# connect.net
KiCad netlist of a schematic drawn in Altium Designer
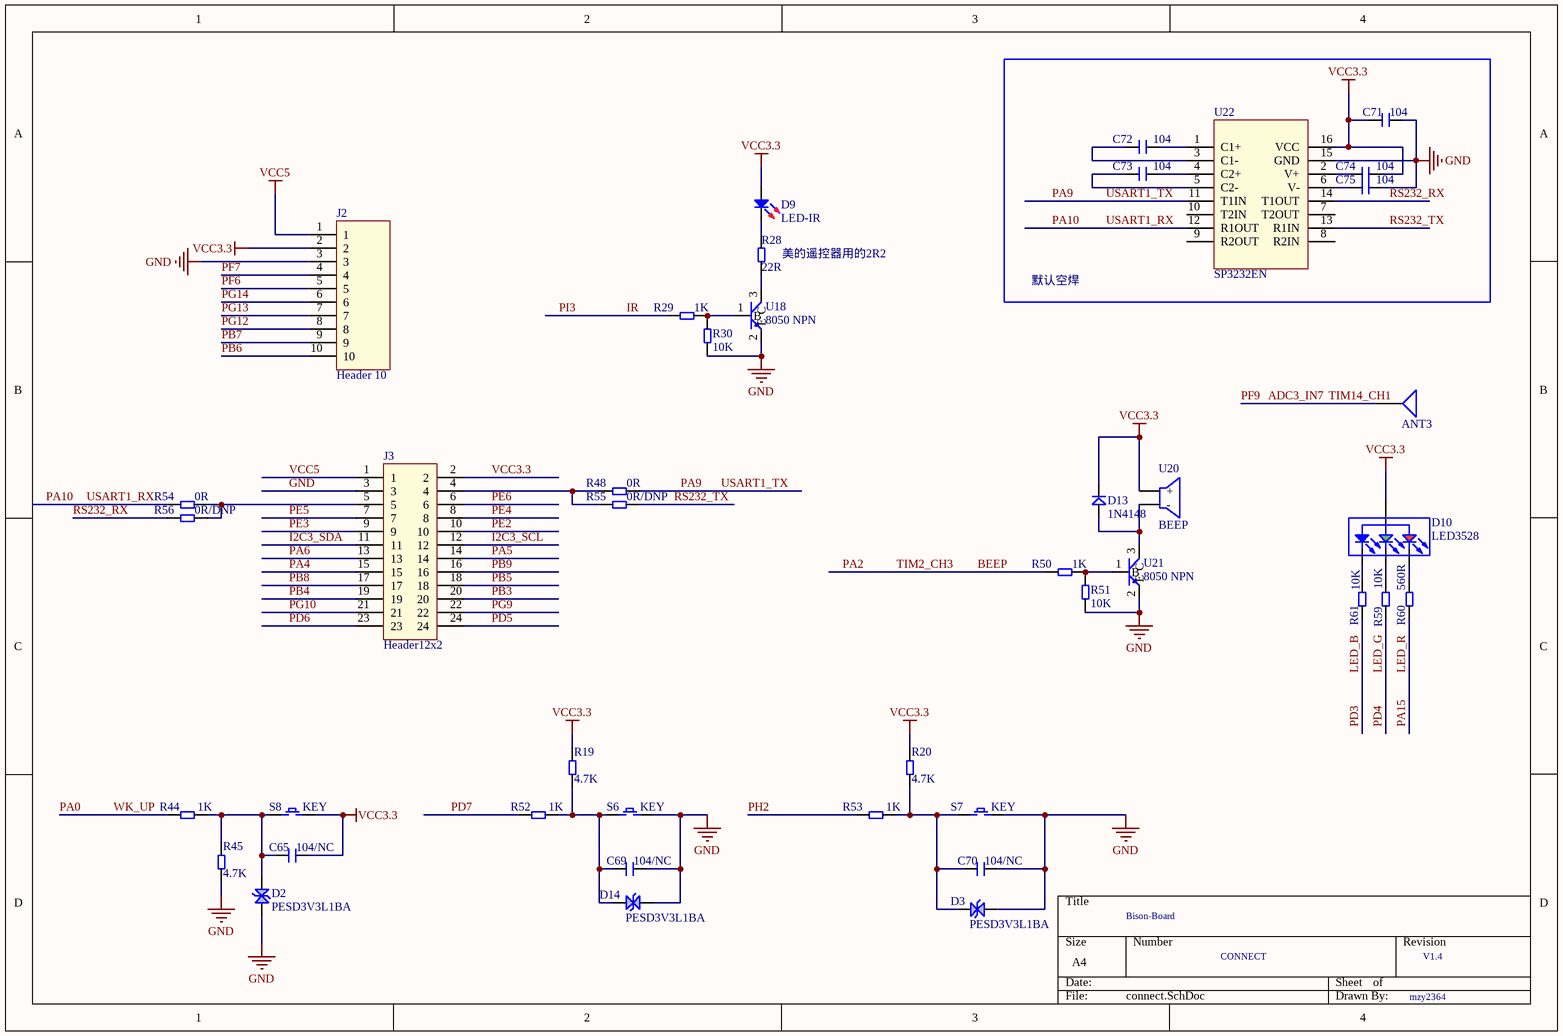
[diagram p0: connect.SchDoc]

(export (version "E")
  (design (tool "Eeschema 10.0.6"))
  (components
    (comp (ref "ANT3") (value "ANT") (footprint "ANT IPEX") (libsource (lib "squ-guiboard") (part "ANT")))
    (comp (ref "C65") (value "104/NC") (footprint "C 0603") (libsource (lib "squ-guiboard") (part "CAP")))
    (comp (ref "C69") (value "104/NC") (footprint "C 0603") (libsource (lib "squ-guiboard") (part "CAP")))
    (comp (ref "C70") (value "104/NC") (footprint "C 0603") (libsource (lib "squ-guiboard") (part "CAP")))
    (comp (ref "C71") (value "104") (footprint "C 0603") (libsource (lib "squ-guiboard") (part "CAP")))
    (comp (ref "C72") (value "104") (footprint "C 0603") (libsource (lib "squ-guiboard") (part "CAP")))
    (comp (ref "C73") (value "104") (footprint "C 0603") (libsource (lib "squ-guiboard") (part "CAP")))
    (comp (ref "C74") (value "104") (footprint "C 0603") (libsource (lib "squ-guiboard") (part "CAP")))
    (comp (ref "C75") (value "104") (footprint "C 0603") (libsource (lib "squ-guiboard") (part "CAP")))
    (comp (ref "D2")
      (value "PESD3V3L1BA")
      (footprint "SOD323")
      (description "双向TVS")
      (libsource (lib "Bison-Board") (part "D Schottky1"))
    )
    (comp (ref "D3")
      (value "PESD3V3L1BA")
      (footprint "SOD323")
      (description "双向TVS")
      (libsource (lib "Bison-Board") (part "D Schottky1"))
    )
    (comp (ref "D9") (value "LED-IR") (footprint "IR12-21C") (libsource (lib "squ-guiboard") (part "LED-IR")))
    (comp (ref "D10")
      (value "LED3528")
      (footprint "LED3528-4PIN")
      (libsource (lib "squ-guiboard") (part "LED3528"))
    )
    (comp (ref "D13") (value "1N4148") (footprint "SOD123") (libsource (lib "squ-guiboard") (part "Diode")))
    (comp (ref "D14")
      (value "PESD3V3L1BA")
      (footprint "SOD323")
      (description "双向TVS")
      (libsource (lib "Bison-Board") (part "D Schottky1"))
    )
    (comp (ref "J2")
      (value "Header 10")
      (footprint "HEADER 10")
      (libsource (lib "Bison-Board") (part "Header 10"))
    )
    (comp (ref "J3")
      (value "Header12x2")
      (footprint "HDR2.54-M-LS-2x12P")
      (libsource (lib "squ-guiboard") (part "Header12x2"))
    )
    (comp (ref "R19") (value "4.7K") (footprint "R 0603") (libsource (lib "squ-guiboard") (part "RES")))
    (comp (ref "R20") (value "4.7K") (footprint "R 0603") (libsource (lib "squ-guiboard") (part "RES")))
    (comp (ref "R28") (value "22R") (footprint "R 0603") (libsource (lib "Bison-Board") (part "RES")))
    (comp (ref "R29") (value "1K") (footprint "R 0603") (libsource (lib "Bison-Board") (part "RES")))
    (comp (ref "R30") (value "10K") (footprint "R 0603") (libsource (lib "Bison-Board") (part "RES")))
    (comp (ref "R44") (value "1K") (footprint "R 0603") (libsource (lib "squ-guiboard") (part "RES")))
    (comp (ref "R45") (value "4.7K") (footprint "R 0603") (libsource (lib "squ-guiboard") (part "RES")))
    (comp (ref "R48") (value "0R") (footprint "R 0603") (libsource (lib "Bison-Board") (part "RES")))
    (comp (ref "R50") (value "1K") (footprint "R 0603") (libsource (lib "Bison-Board") (part "RES")))
    (comp (ref "R51") (value "10K") (footprint "R 0603") (libsource (lib "Bison-Board") (part "RES")))
    (comp (ref "R52") (value "1K") (footprint "R 0603") (libsource (lib "squ-guiboard") (part "RES")))
    (comp (ref "R53") (value "1K") (footprint "R 0603") (libsource (lib "squ-guiboard") (part "RES")))
    (comp (ref "R54") (value "0R") (footprint "R 0603") (libsource (lib "Bison-Board") (part "RES")))
    (comp (ref "R55") (value "0R/DNP") (footprint "R 0603") (libsource (lib "Bison-Board") (part "RES")))
    (comp (ref "R56") (value "0R/DNP") (footprint "R 0603") (libsource (lib "Bison-Board") (part "RES")))
    (comp (ref "R59") (value "10K") (footprint "R 0603") (libsource (lib "squ-guiboard") (part "RES")))
    (comp (ref "R60") (value "560R") (footprint "R 0603") (libsource (lib "squ-guiboard") (part "RES")))
    (comp (ref "R61") (value "10K") (footprint "R 0603") (libsource (lib "squ-guiboard") (part "RES")))
    (comp (ref "S6")
      (value "KEY")
      (footprint "KEY TSW SMD-6*6*6")
      (libsource (lib "Bison-Board") (part "KEY"))
    )
    (comp (ref "S7")
      (value "KEY")
      (footprint "KEY TSW SMD-6*6*6")
      (libsource (lib "Bison-Board") (part "KEY"))
    )
    (comp (ref "S8")
      (value "KEY")
      (footprint "KEY TSW SMD-6*6*6")
      (libsource (lib "Bison-Board") (part "KEY"))
    )
    (comp (ref "U18") (value "8050 NPN") (footprint "SOT23-3") (libsource (lib "squ-guiboard") (part "NPN")))
    (comp (ref "U20") (value "BEEP") (footprint "MLT-5020") (libsource (lib "squ-guiboard") (part "BEEP")))
    (comp (ref "U21") (value "8050 NPN") (footprint "SOT23-3") (libsource (lib "squ-guiboard") (part "NPN")))
    (comp (ref "U22")
      (value "SP3232EN")
      (footprint "TSSOP16")
      (libsource (lib "squ-guiboard") (part "SP3232EN"))
    )
  )
  (nets
    (net (code "1") (name "/ADC3_IN7") (class "Default")
      (node (ref "ANT3") (pin "1") (pinfunction "1_1") (pintype "passive"))
    )
    (net (code "2") (name "/BEEP") (class "Default") (node (ref "R50") (pin "2") (pintype "passive")))
    (net (code "3") (name "/I2C3_SCL") (class "Default")
      (node (ref "J3") (pin "12") (pinfunction "12_12") (pintype "passive"))
    )
    (net (code "4") (name "/I2C3_SDA") (class "Default")
      (node (ref "J3") (pin "11") (pinfunction "11_11") (pintype "passive"))
    )
    (net (code "5") (name "/IR") (class "Default") (node (ref "R29") (pin "2") (pintype "passive")))
    (net (code "6") (name "/LED_B") (class "Default") (node (ref "R61") (pin "1") (pintype "passive")))
    (net (code "7") (name "/LED_G") (class "Default") (node (ref "R59") (pin "1") (pintype "passive")))
    (net (code "8") (name "/LED_R") (class "Default") (node (ref "R60") (pin "1") (pintype "passive")))
    (net (code "9") (name "/PA0") (class "Default") (node (ref "R44") (pin "1") (pintype "passive")))
    (net (code "10") (name "/PA4") (class "Default")
      (node (ref "J3") (pin "15") (pinfunction "15_15") (pintype "passive"))
    )
    (net (code "11") (name "/PA5") (class "Default")
      (node (ref "J3") (pin "14") (pinfunction "14_14") (pintype "passive"))
    )
    (net (code "12") (name "/PA6") (class "Default")
      (node (ref "J3") (pin "13") (pinfunction "13_13") (pintype "passive"))
    )
    (net (code "13") (name "/PA9") (class "Default")
      (node (ref "R48") (pin "1") (pintype "passive"))
      (node (ref "U22") (pin "11") (pinfunction "T1IN_11") (pintype "passive"))
    )
    (net (code "14") (name "/PA10") (class "Default")
      (node (ref "R54") (pin "2") (pintype "passive"))
      (node (ref "U22") (pin "12") (pinfunction "R1OUT_12") (pintype "passive"))
    )
    (net (code "15") (name "/PB3") (class "Default")
      (node (ref "J3") (pin "20") (pinfunction "20_20") (pintype "passive"))
    )
    (net (code "16") (name "/PB4") (class "Default")
      (node (ref "J3") (pin "19") (pinfunction "19_19") (pintype "passive"))
    )
    (net (code "17") (name "/PB5") (class "Default")
      (node (ref "J3") (pin "18") (pinfunction "18_18") (pintype "passive"))
    )
    (net (code "18") (name "/PB6") (class "Default")
      (node (ref "J2") (pin "10") (pinfunction "10_10") (pintype "passive"))
    )
    (net (code "19") (name "/PB7") (class "Default")
      (node (ref "J2") (pin "9") (pinfunction "9_9") (pintype "passive"))
    )
    (net (code "20") (name "/PB8") (class "Default")
      (node (ref "J3") (pin "17") (pinfunction "17_17") (pintype "passive"))
    )
    (net (code "21") (name "/PB9") (class "Default")
      (node (ref "J3") (pin "16") (pinfunction "16_16") (pintype "passive"))
    )
    (net (code "22") (name "/PD5") (class "Default")
      (node (ref "J3") (pin "24") (pinfunction "24_24") (pintype "passive"))
    )
    (net (code "23") (name "/PD6") (class "Default")
      (node (ref "J3") (pin "23") (pinfunction "23_23") (pintype "passive"))
    )
    (net (code "24") (name "/PD7") (class "Default") (node (ref "R52") (pin "1") (pintype "passive")))
    (net (code "25") (name "/PE2") (class "Default")
      (node (ref "J3") (pin "10") (pinfunction "10_10") (pintype "passive"))
    )
    (net (code "26") (name "/PE3") (class "Default")
      (node (ref "J3") (pin "9") (pinfunction "9_9") (pintype "passive"))
    )
    (net (code "27") (name "/PE4") (class "Default")
      (node (ref "J3") (pin "8") (pinfunction "8_8") (pintype "passive"))
    )
    (net (code "28") (name "/PE5") (class "Default")
      (node (ref "J3") (pin "7") (pinfunction "7_7") (pintype "passive"))
    )
    (net (code "29") (name "/PE6") (class "Default")
      (node (ref "J3") (pin "6") (pinfunction "6_6") (pintype "passive"))
    )
    (net (code "30") (name "/PF6") (class "Default")
      (node (ref "J2") (pin "5") (pinfunction "5_5") (pintype "passive"))
    )
    (net (code "31") (name "/PF7") (class "Default")
      (node (ref "J2") (pin "4") (pinfunction "4_4") (pintype "passive"))
    )
    (net (code "32") (name "/PG9") (class "Default")
      (node (ref "J3") (pin "22") (pinfunction "22_22") (pintype "passive"))
    )
    (net (code "33") (name "/PG10") (class "Default")
      (node (ref "J3") (pin "21") (pinfunction "21_21") (pintype "passive"))
    )
    (net (code "34") (name "/PG12") (class "Default")
      (node (ref "J2") (pin "8") (pinfunction "8_8") (pintype "passive"))
    )
    (net (code "35") (name "/PG13") (class "Default")
      (node (ref "J2") (pin "7") (pinfunction "7_7") (pintype "passive"))
    )
    (net (code "36") (name "/PG14") (class "Default")
      (node (ref "J2") (pin "6") (pinfunction "6_6") (pintype "passive"))
    )
    (net (code "37") (name "/PH2") (class "Default") (node (ref "R53") (pin "1") (pintype "passive")))
    (net (code "38") (name "/RS232_RX") (class "Default")
      (node (ref "R56") (pin "2") (pintype "passive"))
      (node (ref "U22") (pin "14") (pinfunction "T1OUT_14") (pintype "passive"))
    )
    (net (code "39") (name "/RS232_TX") (class "Default")
      (node (ref "R55") (pin "1") (pintype "passive"))
      (node (ref "U22") (pin "13") (pinfunction "R1IN_13") (pintype "passive"))
    )
    (net (code "40") (name "GND") (class "Default")
      (node (ref "C69") (pin "2") (pinfunction "2_2") (pintype "passive"))
      (node (ref "C70") (pin "2") (pinfunction "2_2") (pintype "passive"))
      (node (ref "C71") (pin "1") (pinfunction "1_1") (pintype "passive"))
      (node (ref "C75") (pin "2") (pinfunction "2_2") (pintype "passive"))
      (node (ref "D14") (pin "2") (pinfunction "2_2") (pintype "passive"))
      (node (ref "D2") (pin "1") (pinfunction "1_1") (pintype "passive"))
      (node (ref "D3") (pin "2") (pinfunction "2_2") (pintype "passive"))
      (node (ref "J2") (pin "3") (pinfunction "3_3") (pintype "passive"))
      (node (ref "J3") (pin "3") (pinfunction "3_3") (pintype "passive"))
      (node (ref "R30") (pin "2") (pintype "passive"))
      (node (ref "R45") (pin "1") (pintype "passive"))
      (node (ref "R51") (pin "2") (pintype "passive"))
      (node (ref "S6") (pin "2") (pinfunction "2_2") (pintype "passive"))
      (node (ref "S7") (pin "2") (pinfunction "2_2") (pintype "passive"))
      (node (ref "U18") (pin "2") (pinfunction "E_2") (pintype "passive"))
      (node (ref "U21") (pin "2") (pinfunction "E_2") (pintype "passive"))
      (node (ref "U22") (pin "15") (pinfunction "GND_15") (pintype "passive"))
    )
    (net (code "41") (name "Net-(C65-Pad1)") (class "Default")
      (node (ref "C65") (pin "1") (pinfunction "1_1") (pintype "passive"))
      (node (ref "D2") (pin "2") (pinfunction "2_2") (pintype "passive"))
      (node (ref "R44") (pin "2") (pintype "passive"))
      (node (ref "R45") (pin "2") (pintype "passive"))
      (node (ref "S8") (pin "1") (pinfunction "1_1") (pintype "passive"))
    )
    (net (code "42") (name "Net-(C69-Pad1)") (class "Default")
      (node (ref "C69") (pin "1") (pinfunction "1_1") (pintype "passive"))
      (node (ref "D14") (pin "1") (pinfunction "1_1") (pintype "passive"))
      (node (ref "R19") (pin "1") (pintype "passive"))
      (node (ref "R52") (pin "2") (pintype "passive"))
      (node (ref "S6") (pin "1") (pinfunction "1_1") (pintype "passive"))
    )
    (net (code "43") (name "Net-(C70-Pad1)") (class "Default")
      (node (ref "C70") (pin "1") (pinfunction "1_1") (pintype "passive"))
      (node (ref "D3") (pin "1") (pinfunction "1_1") (pintype "passive"))
      (node (ref "R20") (pin "1") (pintype "passive"))
      (node (ref "R53") (pin "2") (pintype "passive"))
      (node (ref "S7") (pin "1") (pinfunction "1_1") (pintype "passive"))
    )
    (net (code "44") (name "Net-(D9-K)") (class "Default")
      (node (ref "D9") (pin "2") (pinfunction "K_2") (pintype "passive"))
      (node (ref "R28") (pin "2") (pintype "passive"))
    )
    (net (code "45") (name "Net-(D10-B)") (class "Default")
      (node (ref "D10") (pin "3") (pinfunction "B_3") (pintype "passive"))
      (node (ref "R61") (pin "2") (pintype "passive"))
    )
    (net (code "46") (name "Net-(D10-G)") (class "Default")
      (node (ref "D10") (pin "4") (pinfunction "G_4") (pintype "passive"))
      (node (ref "R59") (pin "2") (pintype "passive"))
    )
    (net (code "47") (name "Net-(D10-R)") (class "Default")
      (node (ref "D10") (pin "1") (pinfunction "R_1") (pintype "passive"))
      (node (ref "R60") (pin "2") (pintype "passive"))
    )
    (net (code "48") (name "Net-(J3-Pad4)") (class "Default")
      (node (ref "J3") (pin "4") (pinfunction "4_4") (pintype "passive"))
      (node (ref "R48") (pin "2") (pintype "passive"))
      (node (ref "R55") (pin "2") (pintype "passive"))
    )
    (net (code "49") (name "Net-(J3-Pad5)") (class "Default")
      (node (ref "J3") (pin "5") (pinfunction "5_5") (pintype "passive"))
      (node (ref "R54") (pin "1") (pintype "passive"))
      (node (ref "R56") (pin "1") (pintype "passive"))
    )
    (net (code "50") (name "Net-(U18-B)") (class "Default")
      (node (ref "R29") (pin "1") (pintype "passive"))
      (node (ref "R30") (pin "1") (pintype "passive"))
      (node (ref "U18") (pin "1") (pinfunction "B_1") (pintype "passive"))
    )
    (net (code "51") (name "Net-(U18-C)") (class "Default")
      (node (ref "R28") (pin "1") (pintype "passive"))
      (node (ref "U18") (pin "3") (pinfunction "C_3") (pintype "passive"))
    )
    (net (code "52") (name "Net-(U20--)") (class "Default")
      (node (ref "D13") (pin "1") (pintype "passive"))
      (node (ref "U20") (pin "2") (pinfunction "-_2") (pintype "passive"))
      (node (ref "U21") (pin "3") (pinfunction "C_3") (pintype "passive"))
    )
    (net (code "53") (name "Net-(U21-B)") (class "Default")
      (node (ref "R50") (pin "1") (pintype "passive"))
      (node (ref "R51") (pin "1") (pintype "passive"))
      (node (ref "U21") (pin "1") (pinfunction "B_1") (pintype "passive"))
    )
    (net (code "54") (name "Net-(U22-C1+)") (class "Default")
      (node (ref "C72") (pin "2") (pinfunction "2_2") (pintype "passive"))
      (node (ref "U22") (pin "1") (pinfunction "C1+_1") (pintype "passive"))
    )
    (net (code "55") (name "Net-(U22-C1-)") (class "Default")
      (node (ref "C72") (pin "1") (pinfunction "1_1") (pintype "passive"))
      (node (ref "U22") (pin "3") (pinfunction "C1-_3") (pintype "passive"))
    )
    (net (code "56") (name "Net-(U22-C2+)") (class "Default")
      (node (ref "C73") (pin "2") (pinfunction "2_2") (pintype "passive"))
      (node (ref "U22") (pin "4") (pinfunction "C2+_4") (pintype "passive"))
    )
    (net (code "57") (name "Net-(U22-C2-)") (class "Default")
      (node (ref "C73") (pin "1") (pinfunction "1_1") (pintype "passive"))
      (node (ref "U22") (pin "5") (pinfunction "C2-_5") (pintype "passive"))
    )
    (net (code "58") (name "Net-(U22-V+)") (class "Default")
      (node (ref "C74") (pin "1") (pinfunction "1_1") (pintype "passive"))
      (node (ref "U22") (pin "2") (pinfunction "V+_2") (pintype "passive"))
    )
    (net (code "59") (name "Net-(U22-V-)") (class "Default")
      (node (ref "C75") (pin "1") (pinfunction "1_1") (pintype "passive"))
      (node (ref "U22") (pin "6") (pinfunction "V-_6") (pintype "passive"))
    )
    (net (code "60") (name "VCC3.3") (class "Default")
      (node (ref "C65") (pin "2") (pinfunction "2_2") (pintype "passive"))
      (node (ref "C71") (pin "2") (pinfunction "2_2") (pintype "passive"))
      (node (ref "C74") (pin "2") (pinfunction "2_2") (pintype "passive"))
      (node (ref "D10") (pin "2") (pinfunction "+_2") (pintype "passive"))
      (node (ref "D13") (pin "2") (pintype "passive"))
      (node (ref "D9") (pin "1") (pinfunction "A_1") (pintype "passive"))
      (node (ref "J2") (pin "2") (pinfunction "2_2") (pintype "passive"))
      (node (ref "J3") (pin "2") (pinfunction "2_2") (pintype "passive"))
      (node (ref "R19") (pin "2") (pintype "passive"))
      (node (ref "R20") (pin "2") (pintype "passive"))
      (node (ref "S8") (pin "2") (pinfunction "2_2") (pintype "passive"))
      (node (ref "U20") (pin "1") (pinfunction "+_1") (pintype "passive"))
      (node (ref "U22") (pin "16") (pinfunction "VCC_16") (pintype "passive"))
    )
    (net (code "61") (name "VCC5") (class "Default")
      (node (ref "J2") (pin "1") (pinfunction "1_1") (pintype "passive"))
      (node (ref "J3") (pin "1") (pinfunction "1_1") (pintype "passive"))
    )
    (net (code "62") (name "unconnected-(U22-R2IN-Pad8)") (class "Default")
      (node (ref "U22") (pin "8") (pinfunction "R2IN_8") (pintype "passive"))
    )
    (net (code "63") (name "unconnected-(U22-R2OUT-Pad9)") (class "Default")
      (node (ref "U22") (pin "9") (pinfunction "R2OUT_9") (pintype "passive"))
    )
    (net (code "64") (name "unconnected-(U22-T2IN-Pad10)") (class "Default")
      (node (ref "U22") (pin "10") (pinfunction "T2IN_10") (pintype "passive"))
    )
    (net (code "65") (name "unconnected-(U22-T2OUT-Pad7)") (class "Default")
      (node (ref "U22") (pin "7") (pinfunction "T2OUT_7") (pintype "passive"))
    )
  )
)
